# main.net
KiCad netlist of a schematic drawn in Altium Designer
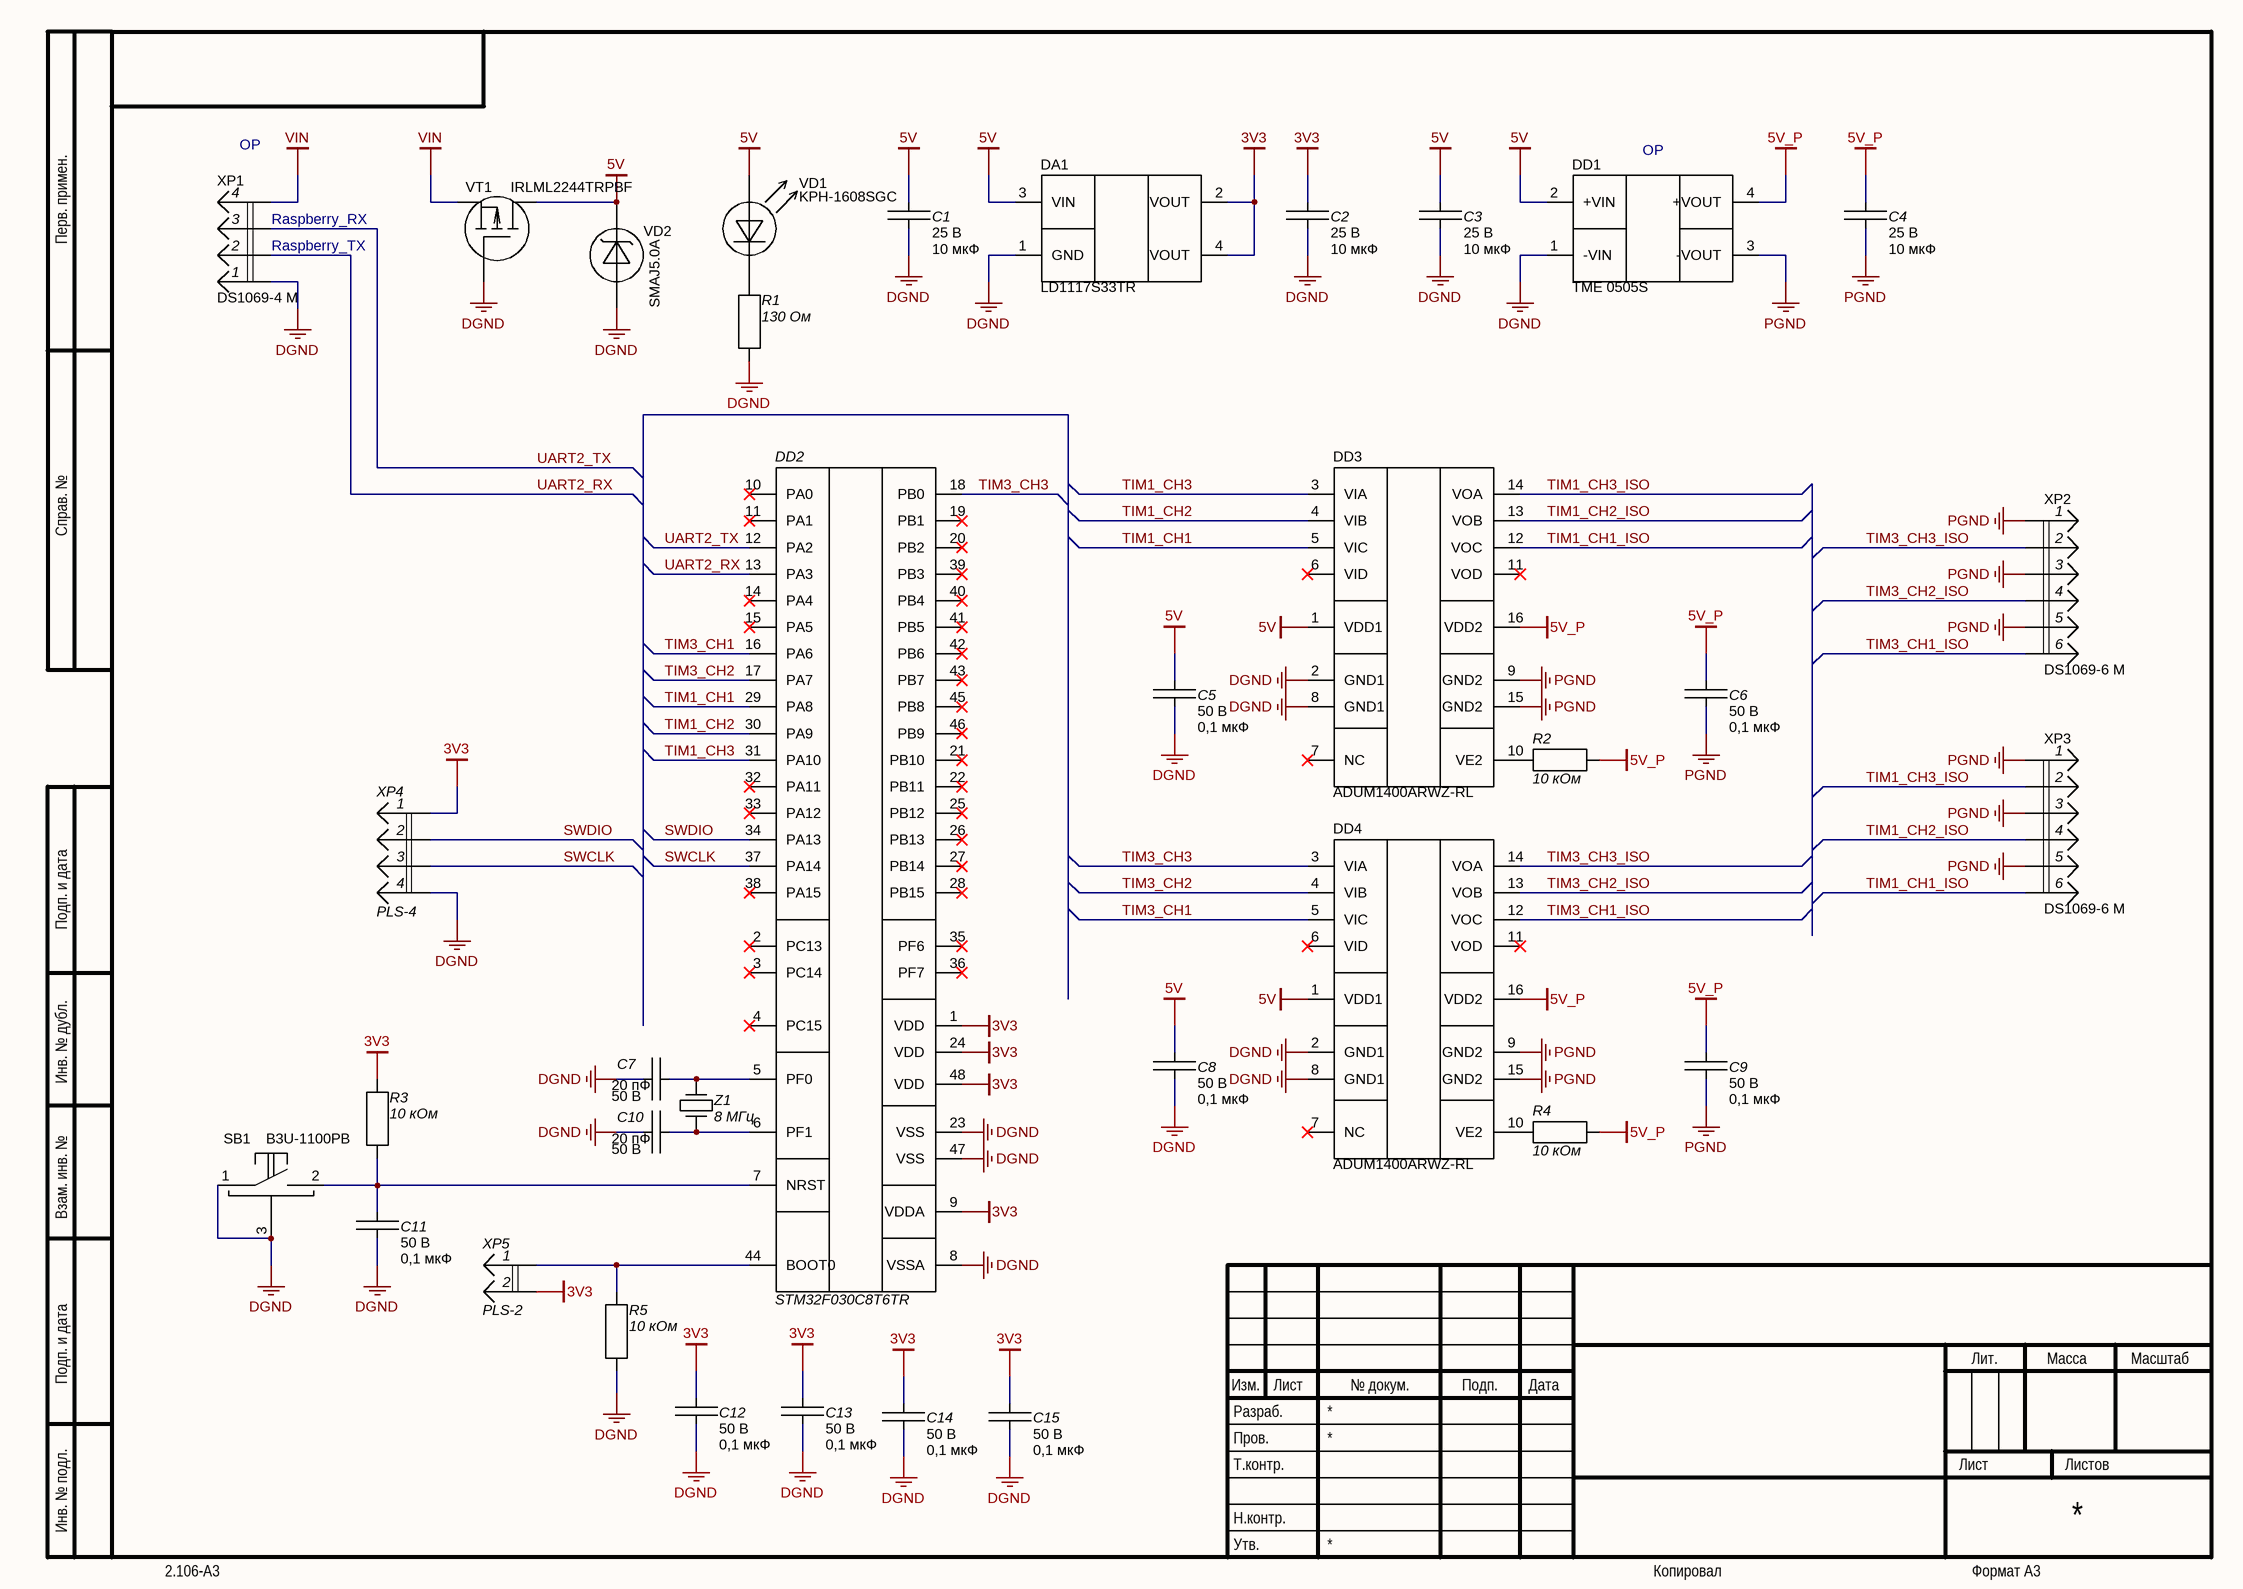
[diagram p0: main.SchDoc]

(export (version "E")
  (design (tool "Eeschema 10.0.6"))
  (components
    (comp (ref "C1")
      (value "10 мкФ")
      (footprint "C1206C")
      (description "SMD 1206; X7R; 10 мкФ; 25 В")
      (fields
        (field (name "PART NUMBER") "CC1206KKX7R8BB106")
        (field (name "MANUFACTURER") "YAGEO")
        (field (name "VOLTAGE") "25 В")
      )
      (libsource (lib "Capacitors") (part "CC1206KKX7R8BB106"))
    )
    (comp (ref "C2")
      (value "10 мкФ")
      (footprint "C1206C")
      (description "SMD 1206; X7R; 10 мкФ; 25 В")
      (fields
        (field (name "PART NUMBER") "CC1206KKX7R8BB106")
        (field (name "MANUFACTURER") "YAGEO")
        (field (name "VOLTAGE") "25 В")
      )
      (libsource (lib "Capacitors") (part "CC1206KKX7R8BB106"))
    )
    (comp (ref "C3")
      (value "10 мкФ")
      (footprint "C1206C")
      (description "SMD 1206; X7R; 10 мкФ; 25 В")
      (fields
        (field (name "PART NUMBER") "CC1206KKX7R8BB106")
        (field (name "MANUFACTURER") "YAGEO")
        (field (name "VOLTAGE") "25 В")
      )
      (libsource (lib "Capacitors") (part "CC1206KKX7R8BB106"))
    )
    (comp (ref "C4")
      (value "10 мкФ")
      (footprint "C1206C")
      (description "SMD 1206; X7R; 10 мкФ; 25 В")
      (fields
        (field (name "PART NUMBER") "CC1206KKX7R8BB106")
        (field (name "MANUFACTURER") "YAGEO")
        (field (name "VOLTAGE") "25 В")
      )
      (libsource (lib "Capacitors") (part "CC1206KKX7R8BB106"))
    )
    (comp (ref "C5")
      (value "0,1 мкФ")
      (footprint "C0603C")
      (description "SMD 0603 ; X7R; 0,1 мкФ; 50 В")
      (fields
        (field (name "PART NUMBER") "CC0603KRX7R9BB104")
        (field (name "MANUFACTURER") "YAGEO")
        (field (name "VOLTAGE") "50 В")
      )
      (libsource (lib "Capacitors") (part "CC0603KRX7R9BB104"))
    )
    (comp (ref "C6")
      (value "0,1 мкФ")
      (footprint "C0603C")
      (description "SMD 0603 ; X7R; 0,1 мкФ; 50 В")
      (fields
        (field (name "PART NUMBER") "CC0603KRX7R9BB104")
        (field (name "MANUFACTURER") "YAGEO")
        (field (name "VOLTAGE") "50 В")
      )
      (libsource (lib "Capacitors") (part "CC0603KRX7R9BB104"))
    )
    (comp (ref "C7")
      (value "20 пФ")
      (footprint "C0603C")
      (description "SMD 0603 ; C0G(NP0); 20 пФ; 50 В")
      (fields
        (field (name "PART NUMBER") "CC0603JRNPO9BN200")
        (field (name "MANUFACTURER") "YAGEO")
        (field (name "VOLTAGE") "50 В")
      )
      (libsource (lib "Capacitors") (part "CC0603JRNPO9BN200"))
    )
    (comp (ref "C8")
      (value "0,1 мкФ")
      (footprint "C0603C")
      (description "SMD 0603 ; X7R; 0,1 мкФ; 50 В")
      (fields
        (field (name "PART NUMBER") "CC0603KRX7R9BB104")
        (field (name "MANUFACTURER") "YAGEO")
        (field (name "VOLTAGE") "50 В")
      )
      (libsource (lib "Capacitors") (part "CC0603KRX7R9BB104"))
    )
    (comp (ref "C9")
      (value "0,1 мкФ")
      (footprint "C0603C")
      (description "SMD 0603 ; X7R; 0,1 мкФ; 50 В")
      (fields
        (field (name "PART NUMBER") "CC0603KRX7R9BB104")
        (field (name "MANUFACTURER") "YAGEO")
        (field (name "VOLTAGE") "50 В")
      )
      (libsource (lib "Capacitors") (part "CC0603KRX7R9BB104"))
    )
    (comp (ref "C10")
      (value "20 пФ")
      (footprint "C0603C")
      (description "SMD 0603 ; C0G(NP0); 20 пФ; 50 В")
      (fields
        (field (name "PART NUMBER") "CC0603JRNPO9BN200")
        (field (name "MANUFACTURER") "YAGEO")
        (field (name "VOLTAGE") "50 В")
      )
      (libsource (lib "Capacitors") (part "CC0603JRNPO9BN200"))
    )
    (comp (ref "C11")
      (value "0,1 мкФ")
      (footprint "C0603C")
      (description "SMD 0603 ; X7R; 0,1 мкФ; 50 В")
      (fields
        (field (name "PART NUMBER") "CC0603KRX7R9BB104")
        (field (name "MANUFACTURER") "YAGEO")
        (field (name "VOLTAGE") "50 В")
      )
      (libsource (lib "Capacitors") (part "CC0603KRX7R9BB104"))
    )
    (comp (ref "C12")
      (value "0,1 мкФ")
      (footprint "C0603C")
      (description "SMD 0603 ; X7R; 0,1 мкФ; 50 В")
      (fields
        (field (name "PART NUMBER") "CC0603KRX7R9BB104")
        (field (name "MANUFACTURER") "YAGEO")
        (field (name "VOLTAGE") "50 В")
      )
      (libsource (lib "Capacitors") (part "CC0603KRX7R9BB104"))
    )
    (comp (ref "C13")
      (value "0,1 мкФ")
      (footprint "C0603C")
      (description "SMD 0603 ; X7R; 0,1 мкФ; 50 В")
      (fields
        (field (name "PART NUMBER") "CC0603KRX7R9BB104")
        (field (name "MANUFACTURER") "YAGEO")
        (field (name "VOLTAGE") "50 В")
      )
      (libsource (lib "Capacitors") (part "CC0603KRX7R9BB104"))
    )
    (comp (ref "C14")
      (value "0,1 мкФ")
      (footprint "C0603C")
      (description "SMD 0603 ; X7R; 0,1 мкФ; 50 В")
      (fields
        (field (name "PART NUMBER") "CC0603KRX7R9BB104")
        (field (name "MANUFACTURER") "YAGEO")
        (field (name "VOLTAGE") "50 В")
      )
      (libsource (lib "Capacitors") (part "CC0603KRX7R9BB104"))
    )
    (comp (ref "C15")
      (value "0,1 мкФ")
      (footprint "C0603C")
      (description "SMD 0603 ; X7R; 0,1 мкФ; 50 В")
      (fields
        (field (name "PART NUMBER") "CC0603KRX7R9BB104")
        (field (name "MANUFACTURER") "YAGEO")
        (field (name "VOLTAGE") "50 В")
      )
      (libsource (lib "Capacitors") (part "CC0603KRX7R9BB104"))
    )
    (comp (ref "DA1")
      (value "LD1117S33TR")
      (footprint "SOT-223")
      (description "Linear regulator, 3V3")
      (fields (field (name "MANUFACTURER") "STMicroelectronics"))
      (libsource (lib "IC") (part "LD1117S33TR"))
    )
    (comp (ref "DD1")
      (value "TME 0505S")
      (footprint "TME-1W-SINGLE")
      (description "Switching regulator, 5V")
      (fields (field (name "MANUFACTURER") "Traco Power"))
      (libsource (lib "IC") (part "TME 0505S"))
    )
    (comp (ref "DD2")
      (value "STM32F030C8T6TR")
      (footprint "LQFP48")
      (fields (field (name "MANUFACTURER") "STMicroelectronics"))
      (libsource (lib "IC") (part "STM32F030C8T6TR"))
    )
    (comp (ref "DD3")
      (value "ADUM1400ARWZ-RL")
      (footprint "SOIC-Wide-16")
      (description "ISO")
      (fields (field (name "MANUFACTURER") "Analog Devices"))
      (libsource (lib "IC") (part "ADUM1400ARWZ-RL"))
    )
    (comp (ref "DD4")
      (value "ADUM1400ARWZ-RL")
      (footprint "SOIC-Wide-16")
      (description "ISO")
      (fields (field (name "MANUFACTURER") "Analog Devices"))
      (libsource (lib "IC") (part "ADUM1400ARWZ-RL"))
    )
    (comp (ref "R1")
      (value "130 Ом")
      (footprint "C0603R")
      (description "SMD 0603; 0,1; 1%; 130 Ом")
      (fields (field (name "PART NUMBER") "RC0603FR-07130RL") (field (name "POWER") "0,1"))
      (libsource (lib "Resistors") (part "RC0603FR-07130RL"))
    )
    (comp (ref "R2")
      (value "10 кОм")
      (footprint "C0603R")
      (description "SMD 0603; 0,1; 1%; 10 кОм")
      (fields (field (name "PART NUMBER") "RC0603FR-0710KL") (field (name "POWER") "0,1"))
      (libsource (lib "Resistors") (part "RC0603FR-0710KL"))
    )
    (comp (ref "R3")
      (value "10 кОм")
      (footprint "C0603R")
      (description "SMD 0603; 0,1; 1%; 10 кОм")
      (fields (field (name "PART NUMBER") "RC0603FR-0710KL") (field (name "POWER") "0,1"))
      (libsource (lib "Resistors") (part "RC0603FR-0710KL"))
    )
    (comp (ref "R4")
      (value "10 кОм")
      (footprint "C0603R")
      (description "SMD 0603; 0,1; 1%; 10 кОм")
      (fields (field (name "PART NUMBER") "RC0603FR-0710KL") (field (name "POWER") "0,1"))
      (libsource (lib "Resistors") (part "RC0603FR-0710KL"))
    )
    (comp (ref "R5")
      (value "10 кОм")
      (footprint "C0603R")
      (description "SMD 0603; 0,1; 1%; 10 кОм")
      (fields (field (name "PART NUMBER") "RC0603FR-0710KL") (field (name "POWER") "0,1"))
      (libsource (lib "Resistors") (part "RC0603FR-0710KL"))
    )
    (comp (ref "SB1")
      (value "B3U-1100PB")
      (footprint "B3U-1100P")
      (description "SB")
      (fields (field (name "MANUFACTURER") "OMRON"))
      (libsource (lib "Conectors") (part "B3U-1100PB"))
    )
    (comp (ref "VD1")
      (value "KPH-1608SGC")
      (footprint "LED_0603")
      (description "0603 LED GREEN 10 ucd")
      (fields (field (name "MANUFACTURER") "Kingbright"))
      (libsource (lib "VD") (part "KPH-1608SGC"))
    )
    (comp (ref "VD2")
      (value "SMAJ5.0A")
      (footprint "DO-214AC")
      (description "TVS 5 В")
      (fields (field (name "VOLTAGE") "5V") (field (name "POWER") "400W"))
      (libsource (lib "VD") (part "SMAJ5.0A"))
    )
    (comp (ref "VT1")
      (value "IRLML2244TRPBF")
      (footprint "SOT23-3")
      (description "P MOSFET")
      (fields (field (name "MANUFACTURER") "Infineon"))
      (libsource (lib "VT") (part "IRLML2244TRPBF"))
    )
    (comp (ref "XP1")
      (value "DS1069-4 M")
      (footprint "DS1069-4 M")
      (fields (field (name "MANUFACTURER") "Connfly"))
      (libsource (lib "Conectors") (part "DS1069-4 M"))
    )
    (comp (ref "XP2")
      (value "DS1069-6 M")
      (footprint "DS1069-6 M")
      (fields (field (name "MANUFACTURER") "Connfly"))
      (libsource (lib "Conectors") (part "DS1069-6 M"))
    )
    (comp (ref "XP3")
      (value "DS1069-6 M")
      (footprint "DS1069-6 M")
      (fields (field (name "MANUFACTURER") "Connfly"))
      (libsource (lib "Conectors") (part "DS1069-6 M"))
    )
    (comp (ref "XP4") (value "PLS-4") (footprint "PLS-4") (libsource (lib "Conectors") (part "PLS-4")))
    (comp (ref "XP5") (value "PLS-2") (footprint "PLS-2") (libsource (lib "Conectors") (part "PLS-2")))
    (comp (ref "Z1")
      (value "8 МГц")
      (footprint "HC-49SM")
      (description "8.000MHzHC-49SM")
      (libsource (lib "IC") (part "8.000MHzHC-49SM"))
    )
  )
  (nets
    (net (code "1") (name "/SWCLK") (class "Default")
      (node (ref "DD2") (pin "37") (pinfunction "PA14_37") (pintype "passive"))
      (node (ref "XP4") (pin "3") (pinfunction "3_3") (pintype "passive"))
    )
    (net (code "2") (name "/SWDIO") (class "Default")
      (node (ref "DD2") (pin "34") (pinfunction "PA13_34") (pintype "passive"))
      (node (ref "XP4") (pin "2") (pinfunction "2_2") (pintype "passive"))
    )
    (net (code "3") (name "/TIM1_CH1") (class "Default")
      (node (ref "DD2") (pin "29") (pinfunction "PA8_29") (pintype "passive"))
      (node (ref "DD3") (pin "5") (pinfunction "VIC_5") (pintype "passive"))
    )
    (net (code "4") (name "/TIM1_CH1_ISO") (class "Default")
      (node (ref "DD3") (pin "12") (pinfunction "VOC_12") (pintype "passive"))
      (node (ref "XP3") (pin "6") (pinfunction "6_6") (pintype "passive"))
    )
    (net (code "5") (name "/TIM1_CH2") (class "Default")
      (node (ref "DD2") (pin "30") (pinfunction "PA9_30") (pintype "passive"))
      (node (ref "DD3") (pin "4") (pinfunction "VIB_4") (pintype "passive"))
    )
    (net (code "6") (name "/TIM1_CH2_ISO") (class "Default")
      (node (ref "DD3") (pin "13") (pinfunction "VOB_13") (pintype "passive"))
      (node (ref "XP3") (pin "4") (pinfunction "4_4") (pintype "passive"))
    )
    (net (code "7") (name "/TIM1_CH3") (class "Default")
      (node (ref "DD2") (pin "31") (pinfunction "PA10_31") (pintype "passive"))
      (node (ref "DD3") (pin "3") (pinfunction "VIA_3") (pintype "passive"))
    )
    (net (code "8") (name "/TIM1_CH3_ISO") (class "Default")
      (node (ref "DD3") (pin "14") (pinfunction "VOA_14") (pintype "passive"))
      (node (ref "XP3") (pin "2") (pinfunction "2_2") (pintype "passive"))
    )
    (net (code "9") (name "/TIM3_CH1") (class "Default")
      (node (ref "DD2") (pin "16") (pinfunction "PA6_16") (pintype "passive"))
      (node (ref "DD4") (pin "5") (pinfunction "VIC_5") (pintype "passive"))
    )
    (net (code "10") (name "/TIM3_CH1_ISO") (class "Default")
      (node (ref "DD4") (pin "12") (pinfunction "VOC_12") (pintype "passive"))
      (node (ref "XP2") (pin "6") (pinfunction "6_6") (pintype "passive"))
    )
    (net (code "11") (name "/TIM3_CH2") (class "Default")
      (node (ref "DD2") (pin "17") (pinfunction "PA7_17") (pintype "passive"))
      (node (ref "DD4") (pin "4") (pinfunction "VIB_4") (pintype "passive"))
    )
    (net (code "12") (name "/TIM3_CH2_ISO") (class "Default")
      (node (ref "DD4") (pin "13") (pinfunction "VOB_13") (pintype "passive"))
      (node (ref "XP2") (pin "4") (pinfunction "4_4") (pintype "passive"))
    )
    (net (code "13") (name "/TIM3_CH3") (class "Default")
      (node (ref "DD2") (pin "18") (pinfunction "PB0_18") (pintype "passive"))
      (node (ref "DD4") (pin "3") (pinfunction "VIA_3") (pintype "passive"))
    )
    (net (code "14") (name "/TIM3_CH3_ISO") (class "Default")
      (node (ref "DD4") (pin "14") (pinfunction "VOA_14") (pintype "passive"))
      (node (ref "XP2") (pin "2") (pinfunction "2_2") (pintype "passive"))
    )
    (net (code "15") (name "/UART2_RX") (class "Default")
      (node (ref "DD2") (pin "13") (pinfunction "PA3_13") (pintype "passive"))
      (node (ref "XP1") (pin "2") (pinfunction "2_2") (pintype "passive"))
    )
    (net (code "16") (name "/UART2_TX") (class "Default")
      (node (ref "DD2") (pin "12") (pinfunction "PA2_12") (pintype "passive"))
      (node (ref "XP1") (pin "3") (pinfunction "3_3") (pintype "passive"))
    )
    (net (code "17") (name "3V3") (class "Default")
      (node (ref "C12") (pin "1") (pinfunction "1_1") (pintype "passive"))
      (node (ref "C13") (pin "1") (pinfunction "1_1") (pintype "passive"))
      (node (ref "C14") (pin "1") (pinfunction "1_1") (pintype "passive"))
      (node (ref "C15") (pin "1") (pinfunction "1_1") (pintype "passive"))
      (node (ref "C2") (pin "1") (pinfunction "1_1") (pintype "passive"))
      (node (ref "DA1") (pin "2") (pinfunction "VOUT_2") (pintype "passive"))
      (node (ref "DA1") (pin "4") (pinfunction "VOUT_4") (pintype "passive"))
      (node (ref "DD2") (pin "1") (pinfunction "VDD_1") (pintype "passive"))
      (node (ref "DD2") (pin "24") (pinfunction "VDD_24") (pintype "passive"))
      (node (ref "DD2") (pin "48") (pinfunction "VDD_48") (pintype "passive"))
      (node (ref "DD2") (pin "9") (pinfunction "VDDA_9") (pintype "passive"))
      (node (ref "R3") (pin "1") (pinfunction "1_1") (pintype "passive"))
      (node (ref "XP4") (pin "1") (pinfunction "1_1") (pintype "passive"))
      (node (ref "XP5") (pin "2") (pinfunction "2_2") (pintype "passive"))
    )
    (net (code "18") (name "5V") (class "Default")
      (node (ref "C1") (pin "1") (pinfunction "1_1") (pintype "passive"))
      (node (ref "C3") (pin "1") (pinfunction "1_1") (pintype "passive"))
      (node (ref "C5") (pin "1") (pinfunction "1_1") (pintype "passive"))
      (node (ref "C8") (pin "1") (pinfunction "1_1") (pintype "passive"))
      (node (ref "DA1") (pin "3") (pinfunction "VIN_3") (pintype "passive"))
      (node (ref "DD1") (pin "2") (pinfunction "+VIN_2") (pintype "power_in"))
      (node (ref "DD3") (pin "1") (pinfunction "VDD1_1") (pintype "passive"))
      (node (ref "DD4") (pin "1") (pinfunction "VDD1_1") (pintype "passive"))
      (node (ref "VD1") (pin "2") (pinfunction "2_2") (pintype "passive"))
      (node (ref "VD2") (pin "1") (pinfunction "C_1") (pintype "passive"))
      (node (ref "VT1") (pin "3") (pinfunction "D_3") (pintype "passive"))
    )
    (net (code "19") (name "5V_P") (class "Default")
      (node (ref "C4") (pin "1") (pinfunction "1_1") (pintype "passive"))
      (node (ref "C6") (pin "1") (pinfunction "1_1") (pintype "passive"))
      (node (ref "C9") (pin "1") (pinfunction "1_1") (pintype "passive"))
      (node (ref "DD1") (pin "4") (pinfunction "+VOUT_4") (pintype "power_in"))
      (node (ref "DD3") (pin "16") (pinfunction "VDD2_16") (pintype "passive"))
      (node (ref "DD4") (pin "16") (pinfunction "VDD2_16") (pintype "passive"))
      (node (ref "R2") (pin "2") (pinfunction "2_2") (pintype "passive"))
      (node (ref "R4") (pin "2") (pinfunction "2_2") (pintype "passive"))
    )
    (net (code "20") (name "DGND") (class "Default")
      (node (ref "C1") (pin "2") (pinfunction "2_2") (pintype "passive"))
      (node (ref "C10") (pin "1") (pinfunction "1_1") (pintype "passive"))
      (node (ref "C11") (pin "2") (pinfunction "2_2") (pintype "passive"))
      (node (ref "C12") (pin "2") (pinfunction "2_2") (pintype "passive"))
      (node (ref "C13") (pin "2") (pinfunction "2_2") (pintype "passive"))
      (node (ref "C14") (pin "2") (pinfunction "2_2") (pintype "passive"))
      (node (ref "C15") (pin "2") (pinfunction "2_2") (pintype "passive"))
      (node (ref "C2") (pin "2") (pinfunction "2_2") (pintype "passive"))
      (node (ref "C3") (pin "2") (pinfunction "2_2") (pintype "passive"))
      (node (ref "C5") (pin "2") (pinfunction "2_2") (pintype "passive"))
      (node (ref "C7") (pin "1") (pinfunction "1_1") (pintype "passive"))
      (node (ref "C8") (pin "2") (pinfunction "2_2") (pintype "passive"))
      (node (ref "DA1") (pin "1") (pinfunction "GND_1") (pintype "passive"))
      (node (ref "DD1") (pin "1") (pinfunction "-VIN_1") (pintype "power_in"))
      (node (ref "DD2") (pin "23") (pinfunction "VSS_23") (pintype "passive"))
      (node (ref "DD2") (pin "47") (pinfunction "VSS_47") (pintype "passive"))
      (node (ref "DD2") (pin "8") (pinfunction "VSSA_8") (pintype "passive"))
      (node (ref "DD3") (pin "2") (pinfunction "GND1_2") (pintype "passive"))
      (node (ref "DD3") (pin "8") (pinfunction "GND1_8") (pintype "passive"))
      (node (ref "DD4") (pin "2") (pinfunction "GND1_2") (pintype "passive"))
      (node (ref "DD4") (pin "8") (pinfunction "GND1_8") (pintype "passive"))
      (node (ref "R1") (pin "2") (pinfunction "2_2") (pintype "passive"))
      (node (ref "R5") (pin "1") (pinfunction "1_1") (pintype "passive"))
      (node (ref "SB1") (pin "1") (pinfunction "1_1") (pintype "passive"))
      (node (ref "SB1") (pin "3") (pinfunction "3_3") (pintype "passive"))
      (node (ref "VD2") (pin "2") (pinfunction "A_2") (pintype "passive"))
      (node (ref "VT1") (pin "1") (pinfunction "G_1") (pintype "passive"))
      (node (ref "XP1") (pin "1") (pinfunction "1_1") (pintype "passive"))
      (node (ref "XP4") (pin "4") (pinfunction "4_4") (pintype "passive"))
    )
    (net (code "21") (name "Net-(DD2-BOOT0)") (class "Default")
      (node (ref "DD2") (pin "44") (pinfunction "BOOT0_44") (pintype "passive"))
      (node (ref "R5") (pin "2") (pinfunction "2_2") (pintype "passive"))
      (node (ref "XP5") (pin "1") (pinfunction "1_1") (pintype "passive"))
    )
    (net (code "22") (name "Net-(DD2-NRST)") (class "Default")
      (node (ref "C11") (pin "1") (pinfunction "1_1") (pintype "passive"))
      (node (ref "DD2") (pin "7") (pinfunction "NRST_7") (pintype "passive"))
      (node (ref "R3") (pin "2") (pinfunction "2_2") (pintype "passive"))
      (node (ref "SB1") (pin "2") (pinfunction "2_2") (pintype "passive"))
    )
    (net (code "23") (name "Net-(DD2-PF0)") (class "Default")
      (node (ref "C7") (pin "2") (pinfunction "2_2") (pintype "passive"))
      (node (ref "DD2") (pin "5") (pinfunction "PF0_5") (pintype "passive"))
      (node (ref "Z1") (pin "2") (pinfunction "OSC2_2") (pintype "passive"))
    )
    (net (code "24") (name "Net-(DD2-PF1)") (class "Default")
      (node (ref "C10") (pin "2") (pinfunction "2_2") (pintype "passive"))
      (node (ref "DD2") (pin "6") (pinfunction "PF1_6") (pintype "passive"))
      (node (ref "Z1") (pin "1") (pinfunction "OSC1_1") (pintype "passive"))
    )
    (net (code "25") (name "Net-(DD3-VE2)") (class "Default")
      (node (ref "DD3") (pin "10") (pinfunction "VE2_10") (pintype "passive"))
      (node (ref "R2") (pin "1") (pinfunction "1_1") (pintype "passive"))
    )
    (net (code "26") (name "Net-(DD4-VE2)") (class "Default")
      (node (ref "DD4") (pin "10") (pinfunction "VE2_10") (pintype "passive"))
      (node (ref "R4") (pin "1") (pinfunction "1_1") (pintype "passive"))
    )
    (net (code "27") (name "Net-(R1-Pad1)") (class "Default")
      (node (ref "R1") (pin "1") (pinfunction "1_1") (pintype "passive"))
      (node (ref "VD1") (pin "1") (pinfunction "1_1") (pintype "passive"))
    )
    (net (code "28") (name "PGND") (class "Default")
      (node (ref "C4") (pin "2") (pinfunction "2_2") (pintype "passive"))
      (node (ref "C6") (pin "2") (pinfunction "2_2") (pintype "passive"))
      (node (ref "C9") (pin "2") (pinfunction "2_2") (pintype "passive"))
      (node (ref "DD1") (pin "3") (pinfunction "-VOUT_3") (pintype "power_in"))
      (node (ref "DD3") (pin "15") (pinfunction "GND2_15") (pintype "passive"))
      (node (ref "DD3") (pin "9") (pinfunction "GND2_9") (pintype "passive"))
      (node (ref "DD4") (pin "15") (pinfunction "GND2_15") (pintype "passive"))
      (node (ref "DD4") (pin "9") (pinfunction "GND2_9") (pintype "passive"))
      (node (ref "XP2") (pin "1") (pinfunction "1_1") (pintype "passive"))
      (node (ref "XP2") (pin "3") (pinfunction "3_3") (pintype "passive"))
      (node (ref "XP2") (pin "5") (pinfunction "5_5") (pintype "passive"))
      (node (ref "XP3") (pin "1") (pinfunction "1_1") (pintype "passive"))
      (node (ref "XP3") (pin "3") (pinfunction "3_3") (pintype "passive"))
      (node (ref "XP3") (pin "5") (pinfunction "5_5") (pintype "passive"))
    )
    (net (code "29") (name "VIN") (class "Default")
      (node (ref "VT1") (pin "2") (pinfunction "S_2") (pintype "passive"))
      (node (ref "XP1") (pin "4") (pinfunction "4_4") (pintype "passive"))
    )
    (net (code "30") (name "unconnected-(DD2-PA0-Pad10)") (class "Default")
      (node (ref "DD2") (pin "10") (pinfunction "PA0_10") (pintype "passive+no_connect"))
    )
    (net (code "31") (name "unconnected-(DD2-PA1-Pad11)") (class "Default")
      (node (ref "DD2") (pin "11") (pinfunction "PA1_11") (pintype "passive+no_connect"))
    )
    (net (code "32") (name "unconnected-(DD2-PA4-Pad14)") (class "Default")
      (node (ref "DD2") (pin "14") (pinfunction "PA4_14") (pintype "passive+no_connect"))
    )
    (net (code "33") (name "unconnected-(DD2-PA5-Pad15)") (class "Default")
      (node (ref "DD2") (pin "15") (pinfunction "PA5_15") (pintype "passive+no_connect"))
    )
    (net (code "34") (name "unconnected-(DD2-PA11-Pad32)") (class "Default")
      (node (ref "DD2") (pin "32") (pinfunction "PA11_32") (pintype "passive+no_connect"))
    )
    (net (code "35") (name "unconnected-(DD2-PA12-Pad33)") (class "Default")
      (node (ref "DD2") (pin "33") (pinfunction "PA12_33") (pintype "passive+no_connect"))
    )
    (net (code "36") (name "unconnected-(DD2-PA15-Pad38)") (class "Default")
      (node (ref "DD2") (pin "38") (pinfunction "PA15_38") (pintype "passive+no_connect"))
    )
    (net (code "37") (name "unconnected-(DD2-PB1-Pad19)") (class "Default")
      (node (ref "DD2") (pin "19") (pinfunction "PB1_19") (pintype "passive+no_connect"))
    )
    (net (code "38") (name "unconnected-(DD2-PB2-Pad20)") (class "Default")
      (node (ref "DD2") (pin "20") (pinfunction "PB2_20") (pintype "passive+no_connect"))
    )
    (net (code "39") (name "unconnected-(DD2-PB3-Pad39)") (class "Default")
      (node (ref "DD2") (pin "39") (pinfunction "PB3_39") (pintype "passive+no_connect"))
    )
    (net (code "40") (name "unconnected-(DD2-PB4-Pad40)") (class "Default")
      (node (ref "DD2") (pin "40") (pinfunction "PB4_40") (pintype "passive+no_connect"))
    )
    (net (code "41") (name "unconnected-(DD2-PB5-Pad41)") (class "Default")
      (node (ref "DD2") (pin "41") (pinfunction "PB5_41") (pintype "passive+no_connect"))
    )
    (net (code "42") (name "unconnected-(DD2-PB6-Pad42)") (class "Default")
      (node (ref "DD2") (pin "42") (pinfunction "PB6_42") (pintype "passive+no_connect"))
    )
    (net (code "43") (name "unconnected-(DD2-PB7-Pad43)") (class "Default")
      (node (ref "DD2") (pin "43") (pinfunction "PB7_43") (pintype "passive+no_connect"))
    )
    (net (code "44") (name "unconnected-(DD2-PB8-Pad45)") (class "Default")
      (node (ref "DD2") (pin "45") (pinfunction "PB8_45") (pintype "passive+no_connect"))
    )
    (net (code "45") (name "unconnected-(DD2-PB9-Pad46)") (class "Default")
      (node (ref "DD2") (pin "46") (pinfunction "PB9_46") (pintype "passive+no_connect"))
    )
    (net (code "46") (name "unconnected-(DD2-PB10-Pad21)") (class "Default")
      (node (ref "DD2") (pin "21") (pinfunction "PB10_21") (pintype "passive+no_connect"))
    )
    (net (code "47") (name "unconnected-(DD2-PB11-Pad22)") (class "Default")
      (node (ref "DD2") (pin "22") (pinfunction "PB11_22") (pintype "passive+no_connect"))
    )
    (net (code "48") (name "unconnected-(DD2-PB12-Pad25)") (class "Default")
      (node (ref "DD2") (pin "25") (pinfunction "PB12_25") (pintype "passive+no_connect"))
    )
    (net (code "49") (name "unconnected-(DD2-PB13-Pad26)") (class "Default")
      (node (ref "DD2") (pin "26") (pinfunction "PB13_26") (pintype "passive+no_connect"))
    )
    (net (code "50") (name "unconnected-(DD2-PB14-Pad27)") (class "Default")
      (node (ref "DD2") (pin "27") (pinfunction "PB14_27") (pintype "passive+no_connect"))
    )
    (net (code "51") (name "unconnected-(DD2-PB15-Pad28)") (class "Default")
      (node (ref "DD2") (pin "28") (pinfunction "PB15_28") (pintype "passive+no_connect"))
    )
    (net (code "52") (name "unconnected-(DD2-PC13-Pad2)") (class "Default")
      (node (ref "DD2") (pin "2") (pinfunction "PC13_2") (pintype "passive+no_connect"))
    )
    (net (code "53") (name "unconnected-(DD2-PC14-Pad3)") (class "Default")
      (node (ref "DD2") (pin "3") (pinfunction "PC14_3") (pintype "passive+no_connect"))
    )
    (net (code "54") (name "unconnected-(DD2-PC15-Pad4)") (class "Default")
      (node (ref "DD2") (pin "4") (pinfunction "PC15_4") (pintype "passive+no_connect"))
    )
    (net (code "55") (name "unconnected-(DD2-PF6-Pad35)") (class "Default")
      (node (ref "DD2") (pin "35") (pinfunction "PF6_35") (pintype "passive+no_connect"))
    )
    (net (code "56") (name "unconnected-(DD2-PF7-Pad36)") (class "Default")
      (node (ref "DD2") (pin "36") (pinfunction "PF7_36") (pintype "passive+no_connect"))
    )
    (net (code "57") (name "unconnected-(DD3-NC-Pad7)") (class "Default")
      (node (ref "DD3") (pin "7") (pinfunction "NC_7") (pintype "passive+no_connect"))
    )
    (net (code "58") (name "unconnected-(DD3-VID-Pad6)") (class "Default")
      (node (ref "DD3") (pin "6") (pinfunction "VID_6") (pintype "passive+no_connect"))
    )
    (net (code "59") (name "unconnected-(DD3-VOD-Pad11)") (class "Default")
      (node (ref "DD3") (pin "11") (pinfunction "VOD_11") (pintype "passive+no_connect"))
    )
    (net (code "60") (name "unconnected-(DD4-NC-Pad7)") (class "Default")
      (node (ref "DD4") (pin "7") (pinfunction "NC_7") (pintype "passive+no_connect"))
    )
    (net (code "61") (name "unconnected-(DD4-VID-Pad6)") (class "Default")
      (node (ref "DD4") (pin "6") (pinfunction "VID_6") (pintype "passive+no_connect"))
    )
    (net (code "62") (name "unconnected-(DD4-VOD-Pad11)") (class "Default")
      (node (ref "DD4") (pin "11") (pinfunction "VOD_11") (pintype "passive+no_connect"))
    )
  )
)
